# Driver.net
KiCad netlist of a schematic drawn in EAGLE
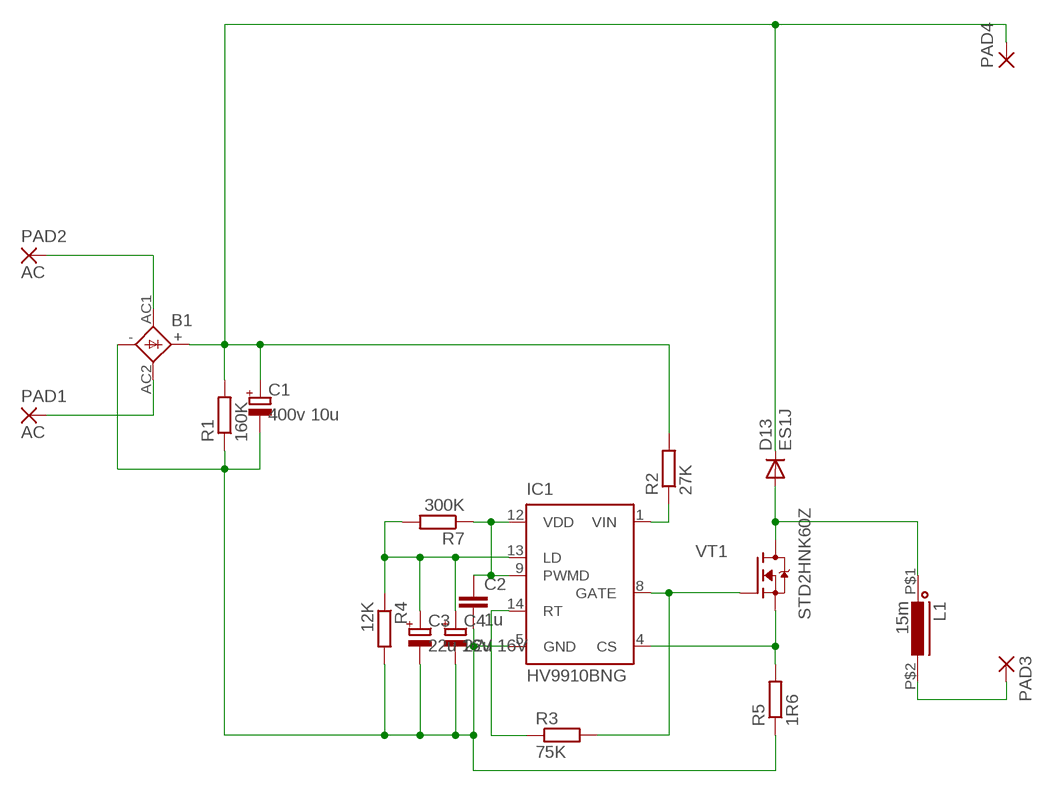
[diagram p0: schematic, sheet 1]

(export (version "E")
  (design (tool "Eeschema 10.0.6"))
  (components
    (comp (ref "B1")
      (value "BRIDGEMBS")
      (footprint "eagle-import:MBS")
      (libsource (lib "eagle-import") (part "BRIDGEMBS"))
    )
    (comp (ref "C1")
      (value "400v 10u")
      (footprint "eagle-import:E3,5-8")
      (libsource (lib "eagle-import") (part "CAP-POL_E3.5-8"))
    )
    (comp (ref "C2")
      (value "1u")
      (footprint "eagle-import:C0805")
      (libsource (lib "eagle-import") (part "CAP_0805"))
    )
    (comp (ref "C3")
      (value "22u 16V")
      (footprint "eagle-import:CT3528")
      (libsource (lib "eagle-import") (part "CAP-POL_3528"))
    )
    (comp (ref "C4")
      (value "22u 16V")
      (footprint "eagle-import:CT3528")
      (libsource (lib "eagle-import") (part "CAP-POL_3528"))
    )
    (comp (ref "D13")
      (value "ES1J")
      (footprint "eagle-import:DO214AC")
      (libsource (lib "eagle-import") (part "DIODE_ES1J"))
    )
    (comp (ref "IC1")
      (value "HV9910BNG")
      (footprint "eagle-import:SOIC-16NG")
      (libsource (lib "eagle-import") (part "HV9910BNG"))
    )
    (comp (ref "L1")
      (value "15m")
      (footprint "eagle-import:SL1016")
      (libsource (lib "eagle-import") (part "INDUCTORSL1016"))
    )
    (comp (ref "PAD1")
      (value "AC")
      (footprint "eagle-import:SMD2,54-5,08")
      (libsource (lib "eagle-import") (part "SMD5"))
    )
    (comp (ref "PAD2")
      (value "AC")
      (footprint "eagle-import:SMD2,54-5,08")
      (libsource (lib "eagle-import") (part "SMD5"))
    )
    (comp (ref "PAD3")
      (value "SMD5")
      (footprint "eagle-import:SMD2,54-5,08")
      (libsource (lib "eagle-import") (part "SMD5"))
    )
    (comp (ref "PAD4")
      (value "SMD5")
      (footprint "eagle-import:SMD2,54-5,08")
      (libsource (lib "eagle-import") (part "SMD5"))
    )
    (comp (ref "R1")
      (value "160K")
      (footprint "eagle-import:MF-0125")
      (libsource (lib "eagle-import") (part "R_MF-0125"))
    )
    (comp (ref "R2")
      (value "27K")
      (footprint "eagle-import:MF-2")
      (libsource (lib "eagle-import") (part "R_MF-2"))
    )
    (comp (ref "R3")
      (value "75K")
      (footprint "eagle-import:R0805")
      (libsource (lib "eagle-import") (part "R_0805"))
    )
    (comp (ref "R4")
      (value "12K")
      (footprint "eagle-import:R0805")
      (libsource (lib "eagle-import") (part "R_0805"))
    )
    (comp (ref "R5")
      (value "1R6")
      (footprint "eagle-import:MF-05")
      (libsource (lib "eagle-import") (part "R_MF-05"))
    )
    (comp (ref "R7")
      (value "300K")
      (footprint "eagle-import:R0805")
      (libsource (lib "eagle-import") (part "R_0805"))
    )
    (comp (ref "VT1")
      (value "STD2HNK60Z")
      (footprint "eagle-import:DPAK")
      (libsource (lib "eagle-import") (part "FET-NDPAK"))
    )
  )
  (nets
    (net (code "1") (name "Net-(IC1-CS)") (class "Default")
      (node (ref "IC1") (pin "4") (pinfunction "CS_4") (pintype "input"))
      (node (ref "R5") (pin "2") (pinfunction "2_2") (pintype "passive"))
      (node (ref "VT1") (pin "S") (pinfunction "S_S") (pintype "passive"))
    )
    (net (code "2") (name "Net-(IC1-GATE)") (class "Default")
      (node (ref "IC1") (pin "8") (pinfunction "GATE_8") (pintype "output"))
      (node (ref "R3") (pin "2") (pinfunction "2_2") (pintype "passive"))
      (node (ref "VT1") (pin "G") (pinfunction "G_G") (pintype "passive"))
    )
    (net (code "3") (name "Net-(IC1-GND)") (class "Default")
      (node (ref "B1") (pin "-") (pinfunction "-_-") (pintype "passive"))
      (node (ref "C1") (pin "-") (pinfunction "-_-") (pintype "passive"))
      (node (ref "C2") (pin "2") (pinfunction "2_2") (pintype "passive"))
      (node (ref "C3") (pin "-") (pinfunction "-_-") (pintype "passive"))
      (node (ref "C4") (pin "-") (pinfunction "-_-") (pintype "passive"))
      (node (ref "IC1") (pin "5") (pinfunction "GND_5") (pintype "power_in"))
      (node (ref "R1") (pin "1") (pinfunction "1_1") (pintype "passive"))
      (node (ref "R4") (pin "2") (pinfunction "2_2") (pintype "passive"))
      (node (ref "R5") (pin "1") (pinfunction "1_1") (pintype "passive"))
    )
    (net (code "4") (name "Net-(IC1-LD)") (class "Default")
      (node (ref "C3") (pin "+") (pinfunction "+_+") (pintype "passive"))
      (node (ref "C4") (pin "+") (pinfunction "+_+") (pintype "passive"))
      (node (ref "IC1") (pin "13") (pinfunction "LD_13") (pintype "input"))
      (node (ref "R4") (pin "1") (pinfunction "1_1") (pintype "passive"))
      (node (ref "R7") (pin "2") (pinfunction "2_2") (pintype "passive"))
    )
    (net (code "5") (name "Net-(IC1-PWMD)") (class "Default")
      (node (ref "C2") (pin "1") (pinfunction "1_1") (pintype "passive"))
      (node (ref "IC1") (pin "12") (pinfunction "VDD_12") (pintype "power_in"))
      (node (ref "IC1") (pin "9") (pinfunction "PWMD_9") (pintype "input"))
      (node (ref "R7") (pin "1") (pinfunction "1_1") (pintype "passive"))
    )
    (net (code "6") (name "Net-(IC1-RT)") (class "Default")
      (node (ref "IC1") (pin "14") (pinfunction "RT_14") (pintype "passive"))
      (node (ref "R3") (pin "1") (pinfunction "1_1") (pintype "passive"))
    )
    (net (code "7") (name "Net-(IC1-VIN)") (class "Default")
      (node (ref "IC1") (pin "1") (pinfunction "VIN_1") (pintype "input"))
      (node (ref "R2") (pin "1") (pinfunction "1_1") (pintype "passive"))
    )
    (net (code "8") (name "Net-(L1-1)") (class "Default")
      (node (ref "D13") (pin "A") (pinfunction "A_A") (pintype "passive"))
      (node (ref "L1") (pin "P$1") (pinfunction "1_P$1") (pintype "passive"))
      (node (ref "VT1") (pin "D") (pinfunction "D_D") (pintype "passive"))
    )
    (net (code "9") (name "Net-(L1-2)") (class "Default")
      (node (ref "L1") (pin "P$2") (pinfunction "2_P$2") (pintype "passive"))
      (node (ref "PAD3") (pin "1") (pinfunction "P_1") (pintype "passive"))
    )
    (net (code "10") (name "Net-(PAD1-P)") (class "Default")
      (node (ref "B1") (pin "AC2") (pinfunction "AC2_AC2") (pintype "passive"))
      (node (ref "PAD1") (pin "1") (pinfunction "P_1") (pintype "passive"))
    )
    (net (code "11") (name "Net-(PAD2-P)") (class "Default")
      (node (ref "B1") (pin "AC1") (pinfunction "AC1_AC1") (pintype "passive"))
      (node (ref "PAD2") (pin "1") (pinfunction "P_1") (pintype "passive"))
    )
    (net (code "12") (name "Net-(PAD4-P)") (class "Default")
      (node (ref "B1") (pin "+") (pinfunction "+_+") (pintype "passive"))
      (node (ref "C1") (pin "+") (pinfunction "+_+") (pintype "passive"))
      (node (ref "D13") (pin "C") (pinfunction "C_C") (pintype "passive"))
      (node (ref "PAD4") (pin "1") (pinfunction "P_1") (pintype "passive"))
      (node (ref "R1") (pin "2") (pinfunction "2_2") (pintype "passive"))
      (node (ref "R2") (pin "2") (pinfunction "2_2") (pintype "passive"))
    )
  )
)
